# 13_iMX_8X_SYSTEM.net
KiCad netlist of a schematic drawn in Altium Designer
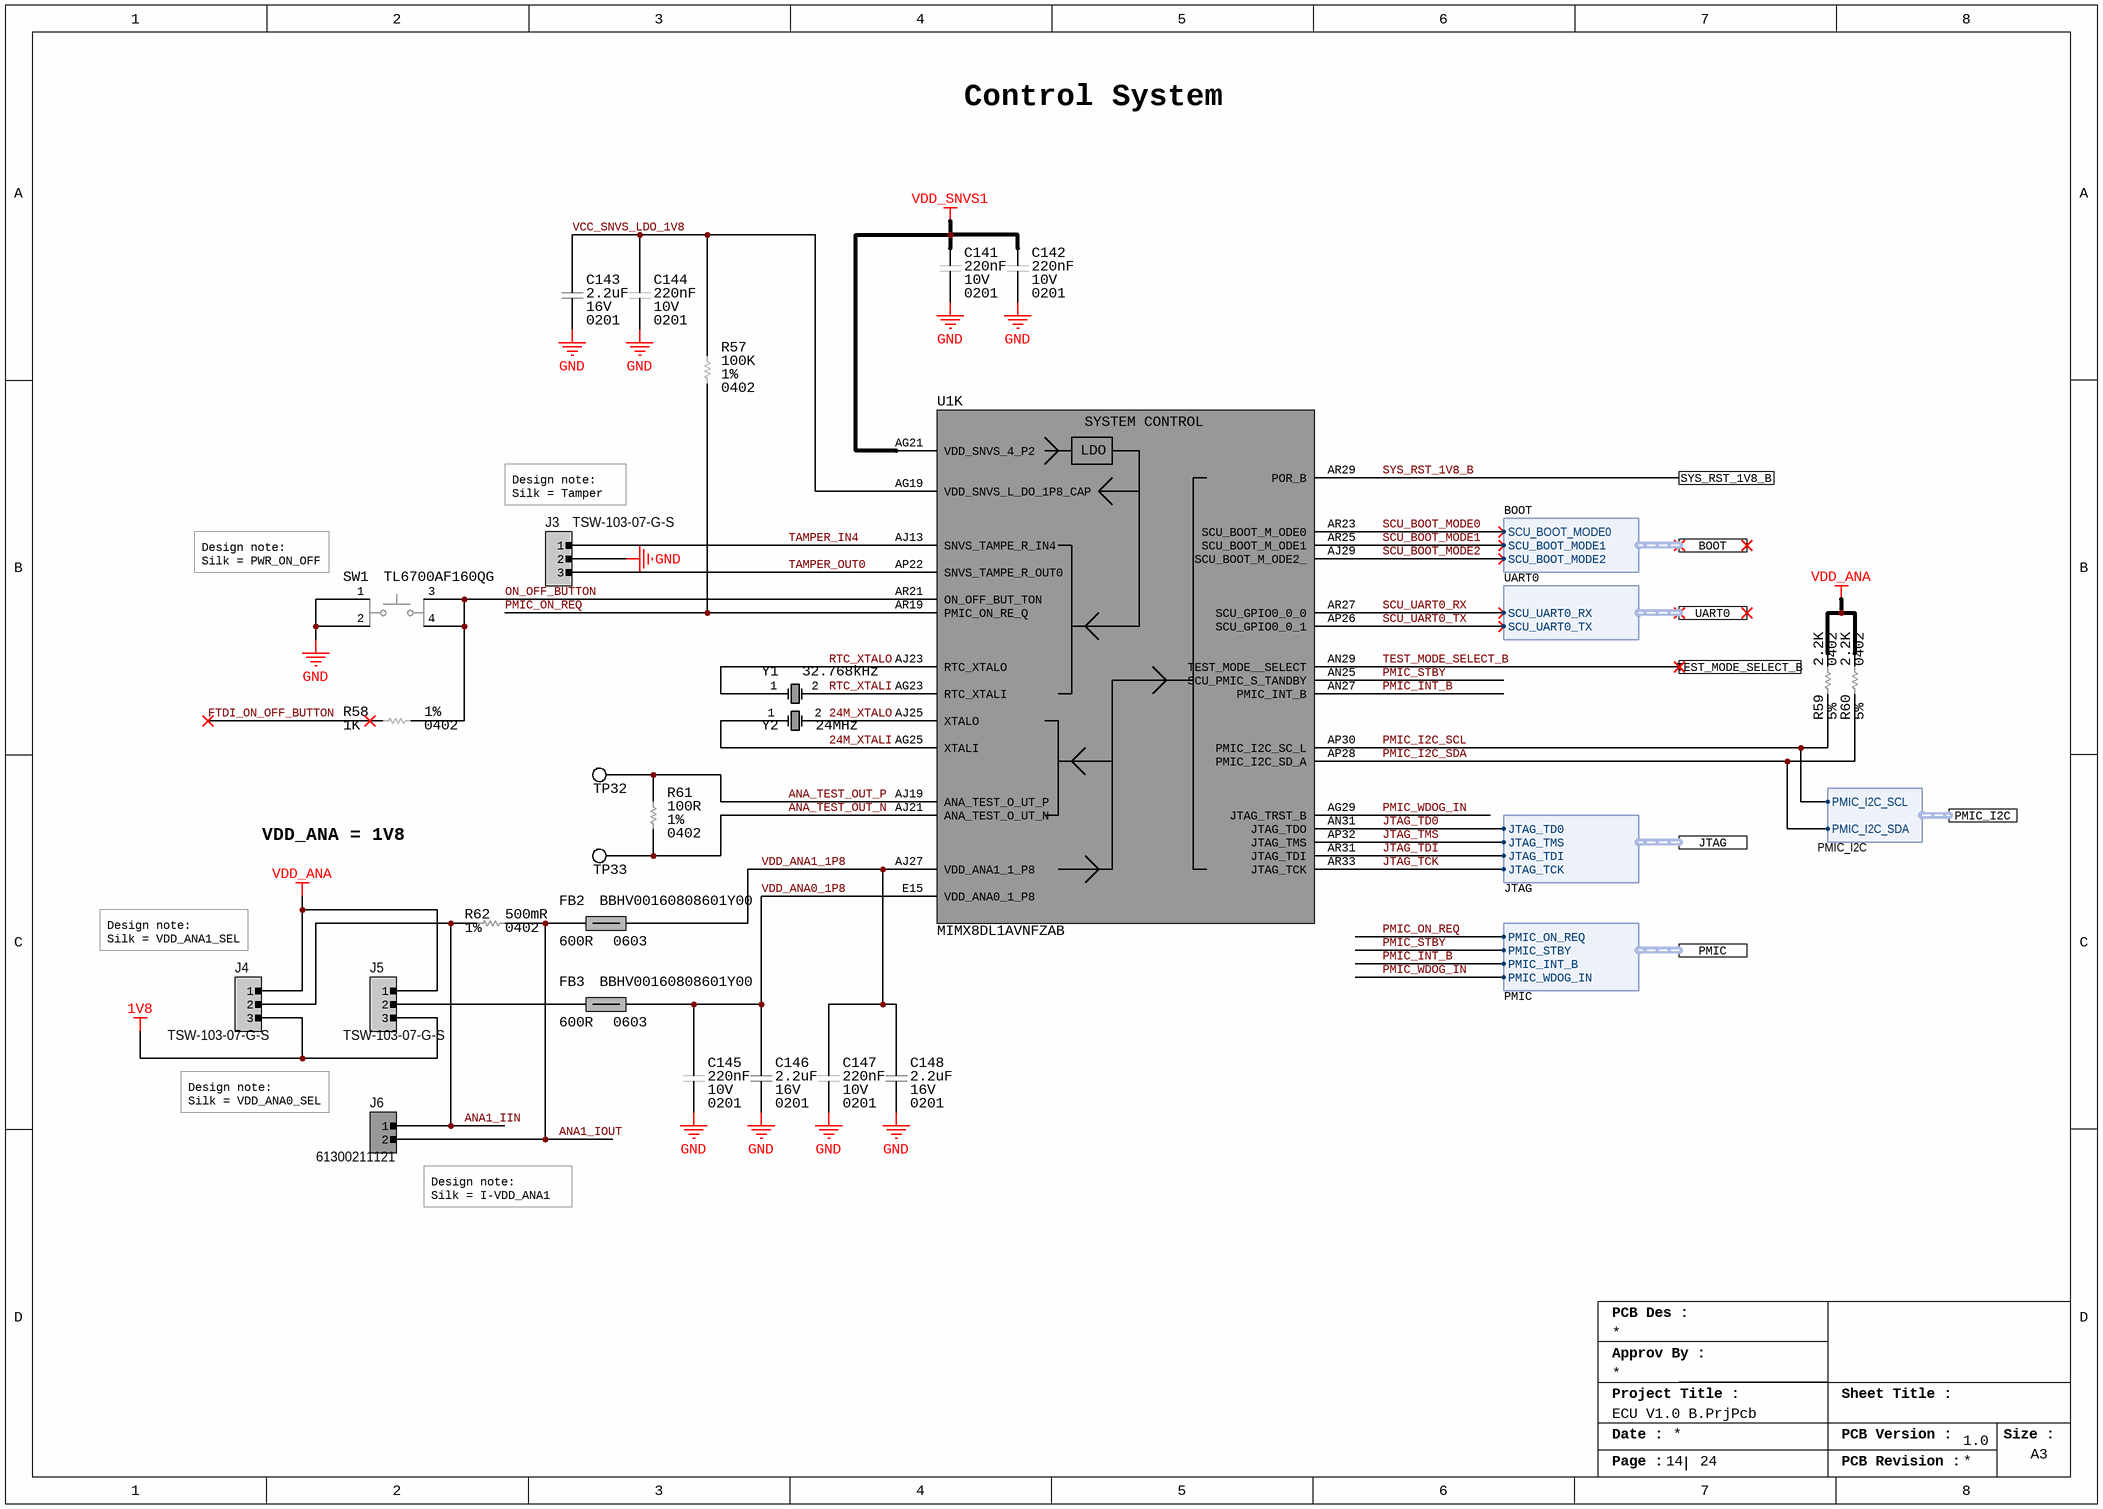
[diagram p0: 13_iMX 8X_SYSTEM.SchDoc]

(export (version "E")
  (design (tool "Eeschema 10.0.6"))
  (components
    (comp (ref "C141")
      (value "LMK063BJ224MP-F")
      (footprint "CAP_0201_CAPC0603X03N")
      (description "Multilayer Ceramic Capacitors (High dielectric type), 10V, 0.22 uF, ± 20 %, 0201, X5R, RoHS")
      (fields
        (field (name "MANUFACTURER") "Taiyo Yuden")
        (field (name "TOLERANCE") "20%")
        (field (name "VOLTAGE RATING (DC)") "10V")
        (field (name "CAPACITANCE") "220nF")
        (field (name "CASE/PACKAGE") "0201")
      )
      (libsource (lib "Electronic Devices_LIB") (part "CAP_0.22UF_10V_X5R_0201"))
    )
    (comp (ref "C142")
      (value "LMK063BJ224MP-F")
      (footprint "CAP_0201_CAPC0603X03N")
      (description "Multilayer Ceramic Capacitors (High dielectric type), 10V, 0.22 uF, ± 20 %, 0201, X5R, RoHS")
      (fields
        (field (name "MANUFACTURER") "Taiyo Yuden")
        (field (name "TOLERANCE") "20%")
        (field (name "VOLTAGE RATING (DC)") "10V")
        (field (name "CAPACITANCE") "220nF")
        (field (name "CASE/PACKAGE") "0201")
      )
      (libsource (lib "Electronic Devices_LIB") (part "CAP_0.22UF_10V_X5R_0201"))
    )
    (comp (ref "C143")
      (value "GRM035R61C225ME01D")
      (footprint "CAP_0201_CAPC0603X03N")
      (description "General Up to 85C Reflow soldering")
      (fields
        (field (name "MANUFACTURER") "Murata")
        (field (name "TOLERANCE") "20%")
        (field (name "CAPACITANCE") "2.2uF")
        (field (name "VOLTAGE RATING") "16V")
        (field (name "CASE/PACKAGE") "0201")
      )
      (libsource (lib "Electronic Devices_LIB") (part "CAP_2.2uF_16V_X5R_0201"))
    )
    (comp (ref "C144")
      (value "LMK063BJ224MP-F")
      (footprint "CAP_0201_CAPC0603X03N")
      (description "Multilayer Ceramic Capacitors (High dielectric type), 10V, 0.22 uF, ± 20 %, 0201, X5R, RoHS")
      (fields
        (field (name "MANUFACTURER") "Taiyo Yuden")
        (field (name "TOLERANCE") "20%")
        (field (name "VOLTAGE RATING (DC)") "10V")
        (field (name "CAPACITANCE") "220nF")
        (field (name "CASE/PACKAGE") "0201")
      )
      (libsource (lib "Electronic Devices_LIB") (part "CAP_0.22UF_10V_X5R_0201"))
    )
    (comp (ref "C145")
      (value "LMK063BJ224MP-F")
      (footprint "CAP_0201_CAPC0603X03N")
      (description "Multilayer Ceramic Capacitors (High dielectric type), 10V, 0.22 uF, ± 20 %, 0201, X5R, RoHS")
      (fields
        (field (name "MANUFACTURER") "Taiyo Yuden")
        (field (name "TOLERANCE") "20%")
        (field (name "VOLTAGE RATING (DC)") "10V")
        (field (name "CAPACITANCE") "220nF")
        (field (name "CASE/PACKAGE") "0201")
      )
      (libsource (lib "Electronic Devices_LIB") (part "CAP_0.22UF_10V_X5R_0201"))
    )
    (comp (ref "C146")
      (value "GRM035R61C225ME01D")
      (footprint "CAP_0201_CAPC0603X03N")
      (description "General Up to 85C Reflow soldering")
      (fields
        (field (name "MANUFACTURER") "Murata")
        (field (name "TOLERANCE") "20%")
        (field (name "CAPACITANCE") "2.2uF")
        (field (name "VOLTAGE RATING") "16V")
        (field (name "CASE/PACKAGE") "0201")
      )
      (libsource (lib "Electronic Devices_LIB") (part "CAP_2.2uF_16V_X5R_0201"))
    )
    (comp (ref "C147")
      (value "LMK063BJ224MP-F")
      (footprint "CAP_0201_CAPC0603X03N")
      (description "Multilayer Ceramic Capacitors (High dielectric type), 10V, 0.22 uF, ± 20 %, 0201, X5R, RoHS")
      (fields
        (field (name "MANUFACTURER") "Taiyo Yuden")
        (field (name "TOLERANCE") "20%")
        (field (name "VOLTAGE RATING (DC)") "10V")
        (field (name "CAPACITANCE") "220nF")
        (field (name "CASE/PACKAGE") "0201")
      )
      (libsource (lib "Electronic Devices_LIB") (part "CAP_0.22UF_10V_X5R_0201"))
    )
    (comp (ref "C148")
      (value "GRM035R61C225ME01D")
      (footprint "CAP_0201_CAPC0603X03N")
      (description "General Up to 85C Reflow soldering")
      (fields
        (field (name "MANUFACTURER") "Murata")
        (field (name "TOLERANCE") "20%")
        (field (name "CAPACITANCE") "2.2uF")
        (field (name "VOLTAGE RATING") "16V")
        (field (name "CASE/PACKAGE") "0201")
      )
      (libsource (lib "Electronic Devices_LIB") (part "CAP_2.2uF_16V_X5R_0201"))
    )
    (comp (ref "FB2")
      (value "BBHV00160808601Y00")
      (footprint "IND_0603_INDC1608X08N")
      (description "Ferrite Chip Bead 600Ohm 2A 0.1Ohm Multilayer 2-Pin 0603 T/R")
      (fields
        (field (name "MANUFACTURER") "Pulse")
        (field (name "IMPEDANCE") "600R")
        (field (name "CASE") "0603")
      )
      (libsource (lib "Electronic Devices_LIB") (part "IND_FERRITE_BEADS_600R_2A_BBHV00160808601Y00"))
    )
    (comp (ref "FB3")
      (value "BBHV00160808601Y00")
      (footprint "IND_0603_INDC1608X08N")
      (description "Ferrite Chip Bead 600Ohm 2A 0.1Ohm Multilayer 2-Pin 0603 T/R")
      (fields
        (field (name "MANUFACTURER") "Pulse")
        (field (name "IMPEDANCE") "600R")
        (field (name "CASE") "0603")
      )
      (libsource (lib "Electronic Devices_LIB") (part "IND_FERRITE_BEADS_600R_2A_BBHV00160808601Y00"))
    )
    (comp (ref "J3")
      (value "TSW-103-07-G-S")
      (footprint "CONN_HEADER_MALE_SAMTEC_TSW-103-07-G-S")
      (description "Conn Unshrouded Header HDR 3 POS 2.54mm Solder ST Top Entry Thru-Hole Bulk")
      (fields (field (name "MANUFACTURER") "Samtec"))
      (libsource (lib "Electronic Devices_LIB") (part "CONN_HEADER_MALE_3P_2.54mm_TSW-103-07-G-S"))
    )
    (comp (ref "J4")
      (value "TSW-103-07-G-S")
      (footprint "CONN_HEADER_MALE_SAMTEC_TSW-103-07-G-S")
      (description "Conn Unshrouded Header HDR 3 POS 2.54mm Solder ST Top Entry Thru-Hole Bulk")
      (fields (field (name "MANUFACTURER") "Samtec"))
      (libsource (lib "Electronic Devices_LIB") (part "CONN_HEADER_MALE_3P_2.54mm_TSW-103-07-G-S"))
    )
    (comp (ref "J5")
      (value "TSW-103-07-G-S")
      (footprint "CONN_HEADER_MALE_SAMTEC_TSW-103-07-G-S")
      (description "Conn Unshrouded Header HDR 3 POS 2.54mm Solder ST Top Entry Thru-Hole Bulk")
      (fields (field (name "MANUFACTURER") "Samtec"))
      (libsource (lib "Electronic Devices_LIB") (part "CONN_HEADER_MALE_3P_2.54mm_TSW-103-07-G-S"))
    )
    (comp (ref "J6")
      (value "61300211121")
      (footprint "HEADER_MALE_HDRV2W110P0X254_1X2_508X254X854P")
      (description "THT Vertical Pin Header WR-PHD, Pitch 2.54 mm, Single Row, 2 pins")
      (fields (field (name "MANUFACTURER") "Wurth Electronics"))
      (libsource (lib "Electronic Devices_LIB") (part "CONN_HEADER_MALE_2P_2.54_61300211121"))
    )
    (comp (ref "R57")
      (value "RC0402FR-07100KL")
      (footprint "RES_0402_RESC1005X04N")
      (description "SMD Chip Resistor, 100 kOhm, ± 1%, 63 mW, 0402 [1005 Metric], Thick Film, General Purpose")
      (fields
        (field (name "MANUFACTURER") "Yageo")
        (field (name "RESISTANCE") "100K")
        (field (name "TOLERANCE") "1%")
        (field (name "CASE/PACKAGE") "0402")
      )
      (libsource (lib "Electronic Devices_LIB") (part "RES_100K_1%_100mW_0402"))
    )
    (comp (ref "R58")
      (value "ERJ-2RKF1001X")
      (footprint "RES_0402_RESC1005X04N")
      (description "RES SMD 1K OHM 1% 1/10W 0402")
      (fields
        (field (name "MANUFACTURER") "Panasonic")
        (field (name "RESISTANCE") "1K")
        (field (name "TOLERANCE") "1%")
        (field (name "CASE/PACKAGE") "0402")
      )
      (libsource (lib "Electronic Devices_LIB") (part "RES_1K_1%_100mW_0402"))
    )
    (comp (ref "R59")
      (value "RC0402JR-072K2L")
      (footprint "RES_0402_RESC1005X04N")
      (description "SMD Chip Resistor, 2.2 kOhm, ± 5%, 63 mW, 0402 [1005 Metric], Thick Film, General Purpose")
      (fields
        (field (name "MANUFACTURER") "Yageo")
        (field (name "TOLERANCE") "5%")
        (field (name "RESISTANCE") "2.2K")
        (field (name "CASE/PACKAGE") "0402")
      )
      (libsource (lib "Electronic Devices_LIB") (part "RES_2.2K_5%_63mW_0402"))
    )
    (comp (ref "R60")
      (value "RC0402JR-072K2L")
      (footprint "RES_0402_RESC1005X04N")
      (description "SMD Chip Resistor, 2.2 kOhm, ± 5%, 63 mW, 0402 [1005 Metric], Thick Film, General Purpose")
      (fields
        (field (name "MANUFACTURER") "Yageo")
        (field (name "TOLERANCE") "5%")
        (field (name "RESISTANCE") "2.2K")
        (field (name "CASE/PACKAGE") "0402")
      )
      (libsource (lib "Electronic Devices_LIB") (part "RES_2.2K_5%_63mW_0402"))
    )
    (comp (ref "R61")
      (value "ERJ-2RKF1000X")
      (footprint "RES_0402_RESC1005X04N")
      (description "Resistor Thick Film 0402 100 Ohm 1% 1/10W 100ppm/C Molded SMD Punched Carrier T/R")
      (fields
        (field (name "MANUFACTURER") "Panasonic")
        (field (name "TOLERANCE") "1%")
        (field (name "RESISTANCE") "100R")
        (field (name "CASE/PACKAGE") "0402")
      )
      (libsource (lib "Electronic Devices_LIB") (part "RES_100R_1%_100mW_0402"))
    )
    (comp (ref "R62")
      (value "RL0402FR-070R5L")
      (footprint "RES_0603_RESC1608X04N")
      (description "SMD Current Sense Resistor, 0.5 ohm, RL Series, 0402 [1005 Metric], 63 mW, ï¿½ 1%, Thick Film")
      (fields
        (field (name "MANUFACTURER") "Yageo")
        (field (name "CASE/PACKAGE") "0402")
        (field (name "TOLERANCE") "1%")
        (field (name "RESISTANCE") "500mR")
      )
      (libsource (lib "Electronic Devices_LIB") (part "RES_0.5R_63mW_0402"))
    )
    (comp (ref "SW1")
      (value "TL6700AF160QG")
      (footprint "SW_TL6700AF160QG")
      (description "TL6700 Series SPST 1.6 N Round Button Gull Wing SMT Sealed Tactile Switch")
      (fields (field (name "MANUFACTURER") "E-Switch"))
      (libsource (lib "Electronic Devices_LIB") (part "SWITCH_SPST_TL6700AF160QG"))
    )
    (comp (ref "TP32")
      (value "NO COMPONENT")
      (footprint "TP_PAD_0.5MM_SMD_ROUND")
      (description "Test Point, SMD pad, round, 1.5mm, 1.6mm, 3mm diameter")
      (libsource (lib "Electronic Devices_LIB") (part "TP_PAD_SMD_SMALL"))
    )
    (comp (ref "TP33")
      (value "NO COMPONENT")
      (footprint "TP_PAD_0.5MM_SMD_ROUND")
      (description "Test Point, SMD pad, round, 1.5mm, 1.6mm, 3mm diameter")
      (libsource (lib "Electronic Devices_LIB") (part "TP_PAD_SMD_SMALL"))
    )
    (comp (ref "U1")
      (value "MIMX8DL1AVNFZAB")
      (footprint "MIMX8DL1AVNFZAB")
      (description "I.MX8 Dxl 15SQ / Tray Rohs Compliant: Yes")
      (fields (field (name "MANUFACTURER") "NXP Semiconductors"))
      (libsource (lib "Electronic Devices_LIB") (part "IC_MPU_ARM_1.2GHz_MIMX8DL1AVNFZAB"))
    )
    (comp (ref "Y1")
      (value "FC-135 32.7680KA-AG5")
      (footprint "CRYSTAL_FC135327680KAAG5")
      (description "Crystal 0.032768MHz ±20ppm (Tol) 7pF FUND 70000Ohm 2-Pin SMD T/R")
      (fields (field (name "MANUFACTURER") "Epson") (field (name "FREQUENCY") "32.768kHz"))
      (libsource (lib "Electronic Devices_LIB") (part "CRYSTAL_EPSON_32.768KHZ"))
    )
    (comp (ref "Y2")
      (value "ECS-240-18-23A-EN-TR")
      (footprint "CRYSTAL_ECS-240-18-23A-EN-TR")
      (description "Crystal 24MHz ±30ppm (Tol) ±50ppm (Stability) 18pF FUND 30Ohm 2-Pin Mini-SMD T/R")
      (fields (field (name "MANUFACTURER") "ECS International") (field (name "FREQUENCY") "24MHz"))
      (libsource (lib "Electronic Devices_LIB") (part "CRYSTAL_ECS_24MHZ"))
    )
  )
  (nets
    (net (code "6") (name "/24M_XTALI") (class "Default")
      (node (ref "U1") (pin "AG25") (pinfunction "XTALI_AG25") (pintype "passive"))
      (node (ref "Y2") (pin "1") (pinfunction "OSC1_1") (pintype "passive"))
    )
    (net (code "7") (name "/24M_XTALO") (class "Default")
      (node (ref "U1") (pin "AJ25") (pinfunction "XTALO_AJ25") (pintype "passive"))
      (node (ref "Y2") (pin "2") (pinfunction "OSC2_2") (pintype "passive"))
    )
    (net (code "8") (name "/ANA1_IIN") (class "Default")
      (node (ref "J4") (pin "2") (pinfunction "2_2") (pintype "passive"))
      (node (ref "J6") (pin "1") (pinfunction "1_1") (pintype "passive"))
      (node (ref "R62") (pin "1") (pinfunction "1_1") (pintype "passive"))
    )
    (net (code "9") (name "/ANA1_IOUT") (class "Default")
      (node (ref "FB2") (pin "1") (pinfunction "1_1") (pintype "passive"))
      (node (ref "J6") (pin "2") (pinfunction "2_2") (pintype "passive"))
      (node (ref "R62") (pin "2") (pinfunction "2_2") (pintype "passive"))
    )
    (net (code "10") (name "/ANA_TEST_OUT_N") (class "Default")
      (node (ref "R61") (pin "1") (pinfunction "1_1") (pintype "passive"))
      (node (ref "TP33") (pin "1") (pinfunction "1_1") (pintype "passive"))
      (node (ref "U1") (pin "AJ21") (pinfunction "ANA_TEST_O_UT_N_AJ21") (pintype "passive"))
    )
    (net (code "11") (name "/ANA_TEST_OUT_P") (class "Default")
      (node (ref "R61") (pin "2") (pinfunction "2_2") (pintype "passive"))
      (node (ref "TP32") (pin "1") (pinfunction "1_1") (pintype "passive"))
      (node (ref "U1") (pin "AJ19") (pinfunction "ANA_TEST_O_UT_P_AJ19") (pintype "passive"))
    )
    (net (code "12") (name "/FTDI_ON_OFF_BUTTON") (class "Default")
      (node (ref "R58") (pin "1") (pinfunction "1_1") (pintype "passive+no_connect"))
    )
    (net (code "13") (name "/JTAG_TCK") (class "Default")
      (node (ref "U1") (pin "AR33") (pinfunction "JTAG_TCK_AR33") (pintype "passive"))
    )
    (net (code "14") (name "/JTAG_TD0") (class "Default")
      (node (ref "U1") (pin "AN31") (pinfunction "JTAG_TDO_AN31") (pintype "passive"))
    )
    (net (code "15") (name "/JTAG_TDI") (class "Default")
      (node (ref "U1") (pin "AR31") (pinfunction "JTAG_TDI_AR31") (pintype "passive"))
    )
    (net (code "16") (name "/JTAG_TMS") (class "Default")
      (node (ref "U1") (pin "AP32") (pinfunction "JTAG_TMS_AP32") (pintype "passive"))
    )
    (net (code "17") (name "/ON_OFF_BUTTON") (class "Default")
      (node (ref "R58") (pin "2") (pinfunction "2_2") (pintype "passive"))
      (node (ref "SW1") (pin "3") (pinfunction "3_3") (pintype "passive"))
      (node (ref "SW1") (pin "4") (pinfunction "4_4") (pintype "passive"))
      (node (ref "U1") (pin "AR21") (pinfunction "ON_OFF_BUT_TON_AR21") (pintype "passive"))
    )
    (net (code "18") (name "/PMIC_I2C_SCL") (class "Default")
      (node (ref "R59") (pin "1") (pinfunction "1_1") (pintype "passive"))
      (node (ref "U1") (pin "AP30") (pinfunction "PMIC_I2C_SC_L_AP30") (pintype "passive"))
    )
    (net (code "19") (name "/PMIC_I2C_SDA") (class "Default")
      (node (ref "R60") (pin "1") (pinfunction "1_1") (pintype "passive"))
      (node (ref "U1") (pin "AP28") (pinfunction "PMIC_I2C_SD_A_AP28") (pintype "passive"))
    )
    (net (code "20") (name "/PMIC_INT_B") (class "Default")
      (node (ref "U1") (pin "AN27") (pinfunction "PMIC_INT_B_AN27") (pintype "passive"))
    )
    (net (code "21") (name "/PMIC_ON_REQ") (class "Default")
      (node (ref "R57") (pin "1") (pinfunction "1_1") (pintype "passive"))
      (node (ref "U1") (pin "AR19") (pinfunction "PMIC_ON_RE_Q_AR19") (pintype "passive"))
    )
    (net (code "22") (name "/PMIC_STBY") (class "Default")
      (node (ref "U1") (pin "AN25") (pinfunction "SCU_PMIC_S_TANDBY_AN25") (pintype "passive"))
    )
    (net (code "23") (name "/PMIC_WDOG_IN") (class "Default")
      (node (ref "U1") (pin "AG29") (pinfunction "JTAG_TRST_B_AG29") (pintype "passive"))
    )
    (net (code "24") (name "/RTC_XTALI") (class "Default")
      (node (ref "U1") (pin "AG23") (pinfunction "RTC_XTALI_AG23") (pintype "passive"))
      (node (ref "Y1") (pin "2") (pinfunction "OSC2_2") (pintype "passive"))
    )
    (net (code "25") (name "/RTC_XTALO") (class "Default")
      (node (ref "U1") (pin "AJ23") (pinfunction "RTC_XTALO_AJ23") (pintype "passive"))
      (node (ref "Y1") (pin "1") (pinfunction "OSC1_1") (pintype "passive"))
    )
    (net (code "26") (name "/SCU_BOOT_MODE0") (class "Default")
      (node (ref "U1") (pin "AR23") (pinfunction "SCU_BOOT_M_ODE0_AR23") (pintype "passive+no_connect"))
    )
    (net (code "27") (name "/SCU_BOOT_MODE1") (class "Default")
      (node (ref "U1") (pin "AR25") (pinfunction "SCU_BOOT_M_ODE1_AR25") (pintype "passive+no_connect"))
    )
    (net (code "28") (name "/SCU_BOOT_MODE2") (class "Default")
      (node (ref "U1") (pin "AJ29") (pinfunction "SCU_BOOT_M_ODE2__AJ29") (pintype "passive+no_connect"))
    )
    (net (code "29") (name "/SCU_UART0_RX") (class "Default")
      (node (ref "U1") (pin "AR27") (pinfunction "SCU_GPIO0_0_0_AR27") (pintype "passive+no_connect"))
    )
    (net (code "30") (name "/SCU_UART0_TX") (class "Default")
      (node (ref "U1") (pin "AP26") (pinfunction "SCU_GPIO0_0_1_AP26") (pintype "passive+no_connect"))
    )
    (net (code "31") (name "/SYS_RST_1V8_B") (class "Default")
      (node (ref "U1") (pin "AR29") (pinfunction "POR_B_AR29") (pintype "passive"))
    )
    (net (code "32") (name "/TAMPER_IN4") (class "Default")
      (node (ref "J3") (pin "1") (pinfunction "1_1") (pintype "passive"))
      (node (ref "U1") (pin "AJ13") (pinfunction "SNVS_TAMPE_R_IN4_AJ13") (pintype "passive"))
    )
    (net (code "33") (name "/TAMPER_OUT0") (class "Default")
      (node (ref "J3") (pin "3") (pinfunction "3_3") (pintype "passive"))
      (node (ref "U1") (pin "AP22") (pinfunction "SNVS_TAMPE_R_OUT0_AP22") (pintype "passive"))
    )
    (net (code "34") (name "/TEST_MODE_SELECT_B") (class "Default")
      (node (ref "U1") (pin "AN29") (pinfunction "TEST_MODE__SELECT_AN29") (pintype "passive+no_connect"))
    )
    (net (code "35") (name "/VCC_SNVS_LDO_1V8") (class "Default")
      (node (ref "C143") (pin "2") (pinfunction "2_2") (pintype "passive"))
      (node (ref "C144") (pin "2") (pinfunction "2_2") (pintype "passive"))
      (node (ref "R57") (pin "2") (pinfunction "2_2") (pintype "passive"))
      (node (ref "U1") (pin "AG19") (pinfunction "VDD_SNVS_L_DO_1P8_CAP_AG19") (pintype "passive"))
    )
    (net (code "36") (name "/VDD_ANA0_1P8") (class "Default")
      (node (ref "C145") (pin "2") (pinfunction "2_2") (pintype "passive"))
      (node (ref "C146") (pin "2") (pinfunction "2_2") (pintype "passive"))
      (node (ref "FB3") (pin "2") (pinfunction "2_2") (pintype "passive"))
      (node (ref "U1") (pin "E15") (pinfunction "VDD_ANA0_1_P8_E15") (pintype "passive"))
    )
    (net (code "37") (name "/VDD_ANA1_1P8") (class "Default")
      (node (ref "C147") (pin "2") (pinfunction "2_2") (pintype "passive"))
      (node (ref "C148") (pin "2") (pinfunction "2_2") (pintype "passive"))
      (node (ref "FB2") (pin "2") (pinfunction "2_2") (pintype "passive"))
      (node (ref "U1") (pin "AJ27") (pinfunction "VDD_ANA1_1_P8_AJ27") (pintype "passive"))
    )
    (net (code "43") (name "1V8") (class "Default")
      (node (ref "J4") (pin "3") (pinfunction "3_3") (pintype "passive"))
      (node (ref "J5") (pin "3") (pinfunction "3_3") (pintype "passive"))
    )
    (net (code "44") (name "GND") (class "Default")
      (node (ref "C141") (pin "1") (pinfunction "1_1") (pintype "passive"))
      (node (ref "C142") (pin "1") (pinfunction "1_1") (pintype "passive"))
      (node (ref "C143") (pin "1") (pinfunction "1_1") (pintype "passive"))
      (node (ref "C144") (pin "1") (pinfunction "1_1") (pintype "passive"))
      (node (ref "C145") (pin "1") (pinfunction "1_1") (pintype "passive"))
      (node (ref "C146") (pin "1") (pinfunction "1_1") (pintype "passive"))
      (node (ref "C147") (pin "1") (pinfunction "1_1") (pintype "passive"))
      (node (ref "C148") (pin "1") (pinfunction "1_1") (pintype "passive"))
      (node (ref "J3") (pin "2") (pinfunction "2_2") (pintype "passive"))
      (node (ref "SW1") (pin "1") (pinfunction "1_1") (pintype "passive"))
      (node (ref "SW1") (pin "2") (pinfunction "2_2") (pintype "passive"))
    )
    (net (code "45") (name "Net-(FB3-Pad1)") (class "Default")
      (node (ref "FB3") (pin "1") (pinfunction "1_1") (pintype "passive"))
      (node (ref "J5") (pin "2") (pinfunction "2_2") (pintype "passive"))
    )
    (net (code "46") (name "VDD_ANA") (class "Default")
      (node (ref "J4") (pin "1") (pinfunction "1_1") (pintype "passive"))
      (node (ref "J5") (pin "1") (pinfunction "1_1") (pintype "passive"))
      (node (ref "R59") (pin "2") (pinfunction "2_2") (pintype "passive"))
      (node (ref "R60") (pin "2") (pinfunction "2_2") (pintype "passive"))
    )
    (net (code "47") (name "VDD_SNVS1") (class "Default")
      (node (ref "C141") (pin "2") (pinfunction "2_2") (pintype "passive"))
      (node (ref "C142") (pin "2") (pinfunction "2_2") (pintype "passive"))
      (node (ref "U1") (pin "AG21") (pinfunction "VDD_SNVS_4_P2_AG21") (pintype "passive"))
    )
  )
)
